# Power.net
KiCad netlist of a schematic drawn in Altium Designer
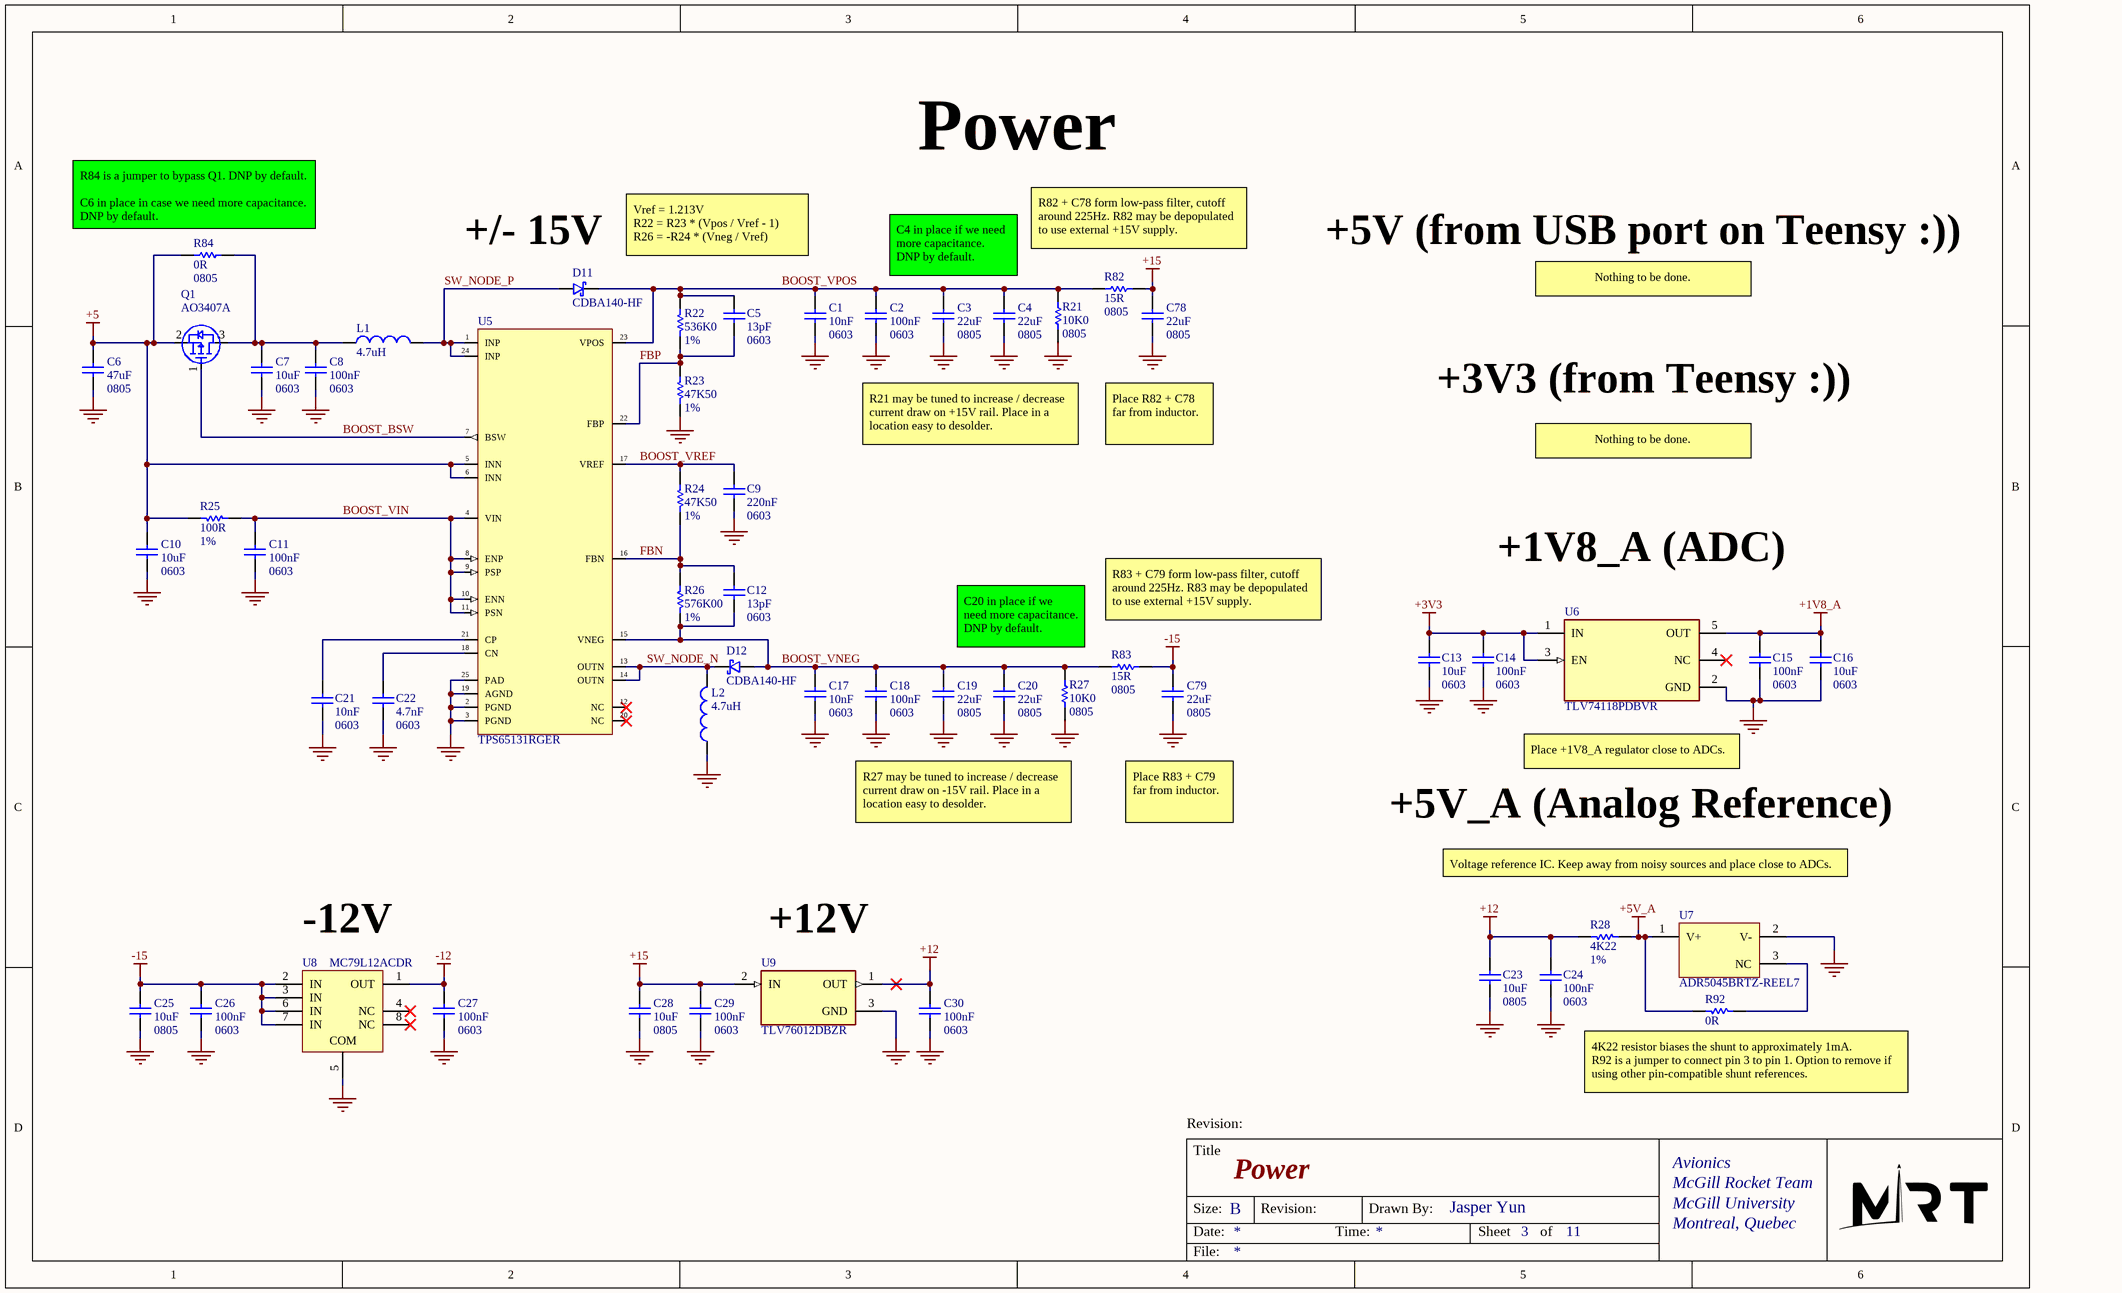
[diagram p0: Power.SchDoc]

(export (version "E")
  (design (tool "Eeschema 10.0.6"))
  (components
    (comp (ref "C1")
      (value "10nF")
      (footprint "0603 CAP SAMSUNG CL10C")
      (description "Capacitor")
      (fields (field (name "ALTIUM_VALUE") "0603") (field (name "PUBLISHER") "Altium Limited"))
      (libsource (lib "Miscellaneous Devices") (part "Cap"))
    )
    (comp (ref "C2")
      (value "100nF")
      (footprint "0603 CAP SAMSUNG CL10C")
      (description "Capacitor")
      (fields (field (name "ALTIUM_VALUE") "0603") (field (name "PUBLISHER") "Altium Limited"))
      (libsource (lib "Miscellaneous Devices") (part "Cap"))
    )
    (comp (ref "C3")
      (value "22uF")
      (footprint "0805 CAP")
      (description "Capacitor")
      (fields (field (name "ALTIUM_VALUE") "0805") (field (name "PUBLISHER") "Altium Limited"))
      (libsource (lib "Miscellaneous Devices") (part "Cap"))
    )
    (comp (ref "C4")
      (value "22uF")
      (footprint "0805 CAP")
      (description "Capacitor")
      (fields (field (name "ALTIUM_VALUE") "0805") (field (name "PUBLISHER") "Altium Limited"))
      (libsource (lib "Miscellaneous Devices") (part "Cap"))
    )
    (comp (ref "C5")
      (value "13pF")
      (footprint "0603 CAP SAMSUNG CL10C")
      (description "Capacitor")
      (fields (field (name "ALTIUM_VALUE") "0603") (field (name "PUBLISHER") "Altium Limited"))
      (libsource (lib "Miscellaneous Devices") (part "Cap"))
    )
    (comp (ref "C6")
      (value "47uF")
      (footprint "0805 CAP")
      (description "Capacitor")
      (fields (field (name "ALTIUM_VALUE") "0805") (field (name "PUBLISHER") "Altium Limited"))
      (libsource (lib "Miscellaneous Devices") (part "Cap"))
    )
    (comp (ref "C7")
      (value "10uF")
      (footprint "0603 CAP SAMSUNG CL10C")
      (description "Capacitor")
      (fields (field (name "ALTIUM_VALUE") "0603") (field (name "PUBLISHER") "Altium Limited"))
      (libsource (lib "Miscellaneous Devices") (part "Cap"))
    )
    (comp (ref "C8")
      (value "100nF")
      (footprint "0603 CAP SAMSUNG CL10C")
      (description "Capacitor")
      (fields (field (name "ALTIUM_VALUE") "0603") (field (name "PUBLISHER") "Altium Limited"))
      (libsource (lib "Miscellaneous Devices") (part "Cap"))
    )
    (comp (ref "C9")
      (value "220nF")
      (footprint "0603 CAP SAMSUNG CL10C")
      (description "Capacitor")
      (fields (field (name "ALTIUM_VALUE") "0603") (field (name "PUBLISHER") "Altium Limited"))
      (libsource (lib "Miscellaneous Devices") (part "Cap"))
    )
    (comp (ref "C10")
      (value "10uF")
      (footprint "0603 CAP SAMSUNG CL10C")
      (description "Capacitor")
      (fields (field (name "ALTIUM_VALUE") "0603") (field (name "PUBLISHER") "Altium Limited"))
      (libsource (lib "Miscellaneous Devices") (part "Cap"))
    )
    (comp (ref "C11")
      (value "100nF")
      (footprint "0603 CAP SAMSUNG CL10C")
      (description "Capacitor")
      (fields (field (name "ALTIUM_VALUE") "0603") (field (name "PUBLISHER") "Altium Limited"))
      (libsource (lib "Miscellaneous Devices") (part "Cap"))
    )
    (comp (ref "C12")
      (value "13pF")
      (footprint "0603 CAP SAMSUNG CL10C")
      (description "Capacitor")
      (fields (field (name "ALTIUM_VALUE") "0603") (field (name "PUBLISHER") "Altium Limited"))
      (libsource (lib "Miscellaneous Devices") (part "Cap"))
    )
    (comp (ref "C13")
      (value "10uF")
      (footprint "0603 CAP SAMSUNG CL10C")
      (description "Capacitor")
      (fields (field (name "ALTIUM_VALUE") "0603") (field (name "PUBLISHER") "Altium Limited"))
      (libsource (lib "Miscellaneous Devices") (part "Cap"))
    )
    (comp (ref "C14")
      (value "100nF")
      (footprint "0603 CAP SAMSUNG CL10C")
      (description "Capacitor")
      (fields (field (name "ALTIUM_VALUE") "0603") (field (name "PUBLISHER") "Altium Limited"))
      (libsource (lib "Miscellaneous Devices") (part "Cap"))
    )
    (comp (ref "C15")
      (value "100nF")
      (footprint "0603 CAP SAMSUNG CL10C")
      (description "Capacitor")
      (fields (field (name "ALTIUM_VALUE") "0603") (field (name "PUBLISHER") "Altium Limited"))
      (libsource (lib "Miscellaneous Devices") (part "Cap"))
    )
    (comp (ref "C16")
      (value "10uF")
      (footprint "0603 CAP SAMSUNG CL10C")
      (description "Capacitor")
      (fields (field (name "ALTIUM_VALUE") "0603") (field (name "PUBLISHER") "Altium Limited"))
      (libsource (lib "Miscellaneous Devices") (part "Cap"))
    )
    (comp (ref "C17")
      (value "10nF")
      (footprint "0603 CAP SAMSUNG CL10C")
      (description "Capacitor")
      (fields (field (name "ALTIUM_VALUE") "0603") (field (name "PUBLISHER") "Altium Limited"))
      (libsource (lib "Miscellaneous Devices") (part "Cap"))
    )
    (comp (ref "C18")
      (value "100nF")
      (footprint "0603 CAP SAMSUNG CL10C")
      (description "Capacitor")
      (fields (field (name "ALTIUM_VALUE") "0603") (field (name "PUBLISHER") "Altium Limited"))
      (libsource (lib "Miscellaneous Devices") (part "Cap"))
    )
    (comp (ref "C19")
      (value "22uF")
      (footprint "0805 CAP")
      (description "Capacitor")
      (fields (field (name "ALTIUM_VALUE") "0805") (field (name "PUBLISHER") "Altium Limited"))
      (libsource (lib "Miscellaneous Devices") (part "Cap"))
    )
    (comp (ref "C20")
      (value "22uF")
      (footprint "0805 CAP")
      (description "Capacitor")
      (fields (field (name "ALTIUM_VALUE") "0805") (field (name "PUBLISHER") "Altium Limited"))
      (libsource (lib "Miscellaneous Devices") (part "Cap"))
    )
    (comp (ref "C21")
      (value "10nF")
      (footprint "0603 CAP SAMSUNG CL10C")
      (description "Capacitor")
      (fields (field (name "ALTIUM_VALUE") "0603") (field (name "PUBLISHER") "Altium Limited"))
      (libsource (lib "Miscellaneous Devices") (part "Cap"))
    )
    (comp (ref "C22")
      (value "4.7nF")
      (footprint "0603 CAP SAMSUNG CL10C")
      (description "Capacitor")
      (fields (field (name "ALTIUM_VALUE") "0603") (field (name "PUBLISHER") "Altium Limited"))
      (libsource (lib "Miscellaneous Devices") (part "Cap"))
    )
    (comp (ref "C23")
      (value "10uF")
      (footprint "0805 CAP")
      (description "Capacitor")
      (fields (field (name "ALTIUM_VALUE") "0805") (field (name "PUBLISHER") "Altium Limited"))
      (libsource (lib "Miscellaneous Devices") (part "Cap"))
    )
    (comp (ref "C24")
      (value "100nF")
      (footprint "0603 CAP SAMSUNG CL10C")
      (description "Capacitor")
      (fields (field (name "ALTIUM_VALUE") "0603") (field (name "PUBLISHER") "Altium Limited"))
      (libsource (lib "Miscellaneous Devices") (part "Cap"))
    )
    (comp (ref "C25")
      (value "10uF")
      (footprint "0805 CAP")
      (description "Capacitor")
      (fields (field (name "ALTIUM_VALUE") "0805") (field (name "PUBLISHER") "Altium Limited"))
      (libsource (lib "Miscellaneous Devices") (part "Cap"))
    )
    (comp (ref "C26")
      (value "100nF")
      (footprint "0603 CAP SAMSUNG CL10C")
      (description "Capacitor")
      (fields (field (name "ALTIUM_VALUE") "0603") (field (name "PUBLISHER") "Altium Limited"))
      (libsource (lib "Miscellaneous Devices") (part "Cap"))
    )
    (comp (ref "C27")
      (value "100nF")
      (footprint "0603 CAP SAMSUNG CL10C")
      (description "Capacitor")
      (fields (field (name "ALTIUM_VALUE") "0603") (field (name "PUBLISHER") "Altium Limited"))
      (libsource (lib "Miscellaneous Devices") (part "Cap"))
    )
    (comp (ref "C28")
      (value "10uF")
      (footprint "0805 CAP")
      (description "Capacitor")
      (fields (field (name "ALTIUM_VALUE") "0805") (field (name "PUBLISHER") "Altium Limited"))
      (libsource (lib "Miscellaneous Devices") (part "Cap"))
    )
    (comp (ref "C29")
      (value "100nF")
      (footprint "0603 CAP SAMSUNG CL10C")
      (description "Capacitor")
      (fields (field (name "ALTIUM_VALUE") "0603") (field (name "PUBLISHER") "Altium Limited"))
      (libsource (lib "Miscellaneous Devices") (part "Cap"))
    )
    (comp (ref "C30")
      (value "100nF")
      (footprint "0603 CAP SAMSUNG CL10C")
      (description "Capacitor")
      (fields (field (name "ALTIUM_VALUE") "0603") (field (name "PUBLISHER") "Altium Limited"))
      (libsource (lib "Miscellaneous Devices") (part "Cap"))
    )
    (comp (ref "C78")
      (value "22uF")
      (footprint "0805 CAP")
      (description "Capacitor")
      (fields (field (name "ALTIUM_VALUE") "0805") (field (name "PUBLISHER") "Altium Limited"))
      (libsource (lib "Miscellaneous Devices") (part "Cap"))
    )
    (comp (ref "C79")
      (value "22uF")
      (footprint "0805 CAP")
      (description "Capacitor")
      (fields (field (name "ALTIUM_VALUE") "0805") (field (name "PUBLISHER") "Altium Limited"))
      (libsource (lib "Miscellaneous Devices") (part "Cap"))
    )
    (comp (ref "D11")
      (value "CDBA140-HF")
      (footprint "Diode SMA")
      (description "Generic Schottky Diode")
      (libsource (lib "MRT SCH Library") (part "Schottky Diode"))
    )
    (comp (ref "D12")
      (value "CDBA140-HF")
      (footprint "Diode SMA")
      (description "Generic Schottky Diode")
      (libsource (lib "MRT SCH Library") (part "Schottky Diode"))
    )
    (comp (ref "L1")
      (value "4.7uH")
      (footprint "Inductor BWVS005050403R3M00")
      (description "4.7uH  BWVS005050404R7M00")
      (fields (field (name "PUBLISHER") "Altium Limited"))
      (libsource (lib "Miscellaneous Devices") (part "Inductor"))
    )
    (comp (ref "L2")
      (value "4.7uH")
      (footprint "Inductor BWVS005050403R3M00")
      (description "4.7uH  BWVS005050404R7M00")
      (fields (field (name "PUBLISHER") "Altium Limited"))
      (libsource (lib "Miscellaneous Devices") (part "Inductor"))
    )
    (comp (ref "Q1")
      (value "AO3407A")
      (footprint "SOT23-3")
      (description "AO3407A PMOS")
      (libsource (lib "MRT SCH Library") (part "PMOS"))
    )
    (comp (ref "R21")
      (value "10K0")
      (footprint "0805 RES")
      (description "Resistor")
      (fields (field (name "ALTIUM_VALUE") "0805") (field (name "PUBLISHER") "Altium Limited"))
      (libsource (lib "Miscellaneous Devices") (part "Res1"))
    )
    (comp (ref "R22")
      (value "536K0")
      (footprint "0603 RES")
      (description "Resistor")
      (fields (field (name "ALTIUM_VALUE") "1%") (field (name "PUBLISHER") "Altium Limited"))
      (libsource (lib "Miscellaneous Devices") (part "Res1"))
    )
    (comp (ref "R23")
      (value "47K50")
      (footprint "0603 RES")
      (description "Resistor")
      (fields (field (name "ALTIUM_VALUE") "1%") (field (name "PUBLISHER") "Altium Limited"))
      (libsource (lib "Miscellaneous Devices") (part "Res1"))
    )
    (comp (ref "R24")
      (value "47K50")
      (footprint "0603 RES")
      (description "Resistor")
      (fields (field (name "ALTIUM_VALUE") "1%") (field (name "PUBLISHER") "Altium Limited"))
      (libsource (lib "Miscellaneous Devices") (part "Res1"))
    )
    (comp (ref "R25")
      (value "100R")
      (footprint "0603 RES")
      (description "Resistor")
      (fields (field (name "ALTIUM_VALUE") "1%") (field (name "PUBLISHER") "Altium Limited"))
      (libsource (lib "Miscellaneous Devices") (part "Res1"))
    )
    (comp (ref "R26")
      (value "576K00")
      (footprint "0603 RES")
      (description "Resistor")
      (fields (field (name "ALTIUM_VALUE") "1%") (field (name "PUBLISHER") "Altium Limited"))
      (libsource (lib "Miscellaneous Devices") (part "Res1"))
    )
    (comp (ref "R27")
      (value "10K0")
      (footprint "0805 RES")
      (description "Resistor")
      (fields (field (name "ALTIUM_VALUE") "0805") (field (name "PUBLISHER") "Altium Limited"))
      (libsource (lib "Miscellaneous Devices") (part "Res1"))
    )
    (comp (ref "R28")
      (value "4K22")
      (footprint "0603 RES")
      (description "Resistor")
      (fields (field (name "ALTIUM_VALUE") "1%") (field (name "PUBLISHER") "Altium Limited"))
      (libsource (lib "Miscellaneous Devices") (part "Res1"))
    )
    (comp (ref "R82")
      (value "15R")
      (footprint "0805 RES")
      (description "Resistor")
      (fields (field (name "ALTIUM_VALUE") "0805") (field (name "PUBLISHER") "Altium Limited"))
      (libsource (lib "Miscellaneous Devices") (part "Res1"))
    )
    (comp (ref "R83")
      (value "15R")
      (footprint "0805 RES")
      (description "Resistor")
      (fields (field (name "ALTIUM_VALUE") "0805") (field (name "PUBLISHER") "Altium Limited"))
      (libsource (lib "Miscellaneous Devices") (part "Res1"))
    )
    (comp (ref "R84")
      (value "0R")
      (footprint "0805 RES")
      (description "Resistor")
      (fields (field (name "ALTIUM_VALUE") "0805") (field (name "PUBLISHER") "Altium Limited"))
      (libsource (lib "Miscellaneous Devices") (part "Res1"))
    )
    (comp (ref "R92")
      (value "0R")
      (footprint "0603 RES")
      (description "Resistor")
      (fields (field (name "PUBLISHER") "Altium Limited"))
      (libsource (lib "Miscellaneous Devices") (part "Res1"))
    )
    (comp (ref "U5")
      (value "TPS65131RGER")
      (footprint "VQFN-24")
      (description "IC REG BUCK BST INV ADJ DL 24QFN")
      (fields (field (name "MANUFACTURER") "Texas Instruments"))
      (libsource (lib "MRT SCH Library") (part "Dual Boost TPS65131RGER"))
    )
    (comp (ref "U6")
      (value "TLV74118PDBVR")
      (footprint "FP-DBV0005A-IPC_A")
      (description "None")
      (libsource (lib "Altium Content Vault") (part "843f007849b3ee74adb27ff62509038"))
    )
    (comp (ref "U7")
      (value "ADR5045BRTZ-REEL7")
      (footprint "ADI-RT-3_M")
      (fields (field (name "MANUFACTURER") "Analog Devices"))
      (libsource (lib "Altium Content Vault") (part "ADI-ADR158x_504x-RT_KS-3"))
    )
    (comp (ref "U8")
      (value "MC79L12ACDR")
      (footprint "D0008A_M")
      (fields (field (name "MANUFACTURER") "Texas Instruments"))
      (libsource (lib "Altium Content Vault") (part "TI-MC79L12AD8"))
    )
    (comp (ref "U9")
      (value "TLV76012DBZR")
      (footprint "FP-DBZ0003A-IPC_A")
      (description "IC REG LINEAR 12V 100MA SOT23-3")
      (libsource (lib "Altium Content Vault") (part "194d833bae470731f3ec9529f7c1b5f"))
    )
  )
  (nets
    (net (code "1") (name "+1V8_A") (class "Default")
      (node (ref "C15") (pin "2") (pinfunction "2_2") (pintype "passive"))
      (node (ref "C16") (pin "2") (pinfunction "2_2") (pintype "passive"))
      (node (ref "U6") (pin "5") (pinfunction "OUT_5") (pintype "power_in"))
    )
    (net (code "2") (name "+3V3") (class "Default")
      (node (ref "C13") (pin "2") (pinfunction "2_2") (pintype "passive"))
      (node (ref "C14") (pin "2") (pinfunction "2_2") (pintype "passive"))
      (node (ref "U6") (pin "1") (pinfunction "IN_1") (pintype "power_in"))
      (node (ref "U6") (pin "3") (pinfunction "EN_3") (pintype "input"))
    )
    (net (code "3") (name "+5") (class "Default")
      (node (ref "C10") (pin "2") (pinfunction "2_2") (pintype "passive"))
      (node (ref "C6") (pin "2") (pinfunction "2_2") (pintype "passive"))
      (node (ref "Q1") (pin "2") (pinfunction "Source_2") (pintype "passive"))
      (node (ref "R25") (pin "1") (pinfunction "1_1") (pintype "passive"))
      (node (ref "R84") (pin "2") (pinfunction "2_2") (pintype "passive"))
      (node (ref "U5") (pin "5") (pinfunction "INN_5") (pintype "passive"))
      (node (ref "U5") (pin "6") (pinfunction "INN_6") (pintype "passive"))
    )
    (net (code "4") (name "+5V_A") (class "Default")
      (node (ref "R28") (pin "2") (pinfunction "2_2") (pintype "passive"))
      (node (ref "R92") (pin "1") (pinfunction "1_1") (pintype "passive"))
      (node (ref "U7") (pin "1") (pinfunction "V+_1") (pintype "power_in"))
    )
    (net (code "5") (name "+12") (class "Default")
      (node (ref "C23") (pin "2") (pinfunction "2_2") (pintype "passive"))
      (node (ref "C24") (pin "2") (pinfunction "2_2") (pintype "passive"))
      (node (ref "C30") (pin "2") (pinfunction "2_2") (pintype "passive"))
      (node (ref "R28") (pin "1") (pinfunction "1_1") (pintype "passive"))
      (node (ref "U9") (pin "1") (pinfunction "OUT_1") (pintype "output"))
    )
    (net (code "6") (name "+15") (class "Default")
      (node (ref "C28") (pin "2") (pinfunction "2_2") (pintype "passive"))
      (node (ref "C29") (pin "2") (pinfunction "2_2") (pintype "passive"))
      (node (ref "C78") (pin "2") (pinfunction "2_2") (pintype "passive"))
      (node (ref "R82") (pin "1") (pinfunction "1_1") (pintype "passive"))
      (node (ref "U9") (pin "2") (pinfunction "IN_2") (pintype "input"))
    )
    (net (code "7") (name "-12") (class "Default")
      (node (ref "C27") (pin "2") (pinfunction "2_2") (pintype "passive"))
      (node (ref "U8") (pin "1") (pinfunction "OUT_1") (pintype "power_in"))
    )
    (net (code "8") (name "-15") (class "Default")
      (node (ref "C25") (pin "2") (pinfunction "2_2") (pintype "passive"))
      (node (ref "C26") (pin "2") (pinfunction "2_2") (pintype "passive"))
      (node (ref "C79") (pin "2") (pinfunction "2_2") (pintype "passive"))
      (node (ref "R83") (pin "1") (pinfunction "1_1") (pintype "passive"))
      (node (ref "U8") (pin "2") (pinfunction "IN_2") (pintype "power_in"))
      (node (ref "U8") (pin "3") (pinfunction "IN_3") (pintype "power_in"))
      (node (ref "U8") (pin "6") (pinfunction "IN_6") (pintype "power_in"))
      (node (ref "U8") (pin "7") (pinfunction "IN_7") (pintype "power_in"))
    )
    (net (code "9") (name "/BOOST_BSW") (class "Default")
      (node (ref "Q1") (pin "1") (pinfunction "Gate_1") (pintype "passive"))
      (node (ref "U5") (pin "7") (pinfunction "BSW_7") (pintype "output"))
    )
    (net (code "10") (name "/BOOST_VIN") (class "Default")
      (node (ref "C11") (pin "2") (pinfunction "2_2") (pintype "passive"))
      (node (ref "R25") (pin "2") (pinfunction "2_2") (pintype "passive"))
      (node (ref "U5") (pin "10") (pinfunction "ENN_10") (pintype "input"))
      (node (ref "U5") (pin "11") (pinfunction "PSN_11") (pintype "input"))
      (node (ref "U5") (pin "4") (pinfunction "VIN_4") (pintype "passive"))
      (node (ref "U5") (pin "8") (pinfunction "ENP_8") (pintype "input"))
      (node (ref "U5") (pin "9") (pinfunction "PSP_9") (pintype "input"))
    )
    (net (code "11") (name "/BOOST_VNEG") (class "Default")
      (node (ref "C12") (pin "1") (pinfunction "1_1") (pintype "passive"))
      (node (ref "C17") (pin "2") (pinfunction "2_2") (pintype "passive"))
      (node (ref "C18") (pin "2") (pinfunction "2_2") (pintype "passive"))
      (node (ref "C19") (pin "2") (pinfunction "2_2") (pintype "passive"))
      (node (ref "C20") (pin "2") (pinfunction "2_2") (pintype "passive"))
      (node (ref "D12") (pin "2") (pinfunction "Anode_2") (pintype "passive"))
      (node (ref "R26") (pin "1") (pinfunction "1_1") (pintype "passive"))
      (node (ref "R27") (pin "2") (pinfunction "2_2") (pintype "passive"))
      (node (ref "R83") (pin "2") (pinfunction "2_2") (pintype "passive"))
      (node (ref "U5") (pin "15") (pinfunction "VNEG_15") (pintype "passive"))
    )
    (net (code "12") (name "/BOOST_VPOS") (class "Default")
      (node (ref "C1") (pin "2") (pinfunction "2_2") (pintype "passive"))
      (node (ref "C2") (pin "2") (pinfunction "2_2") (pintype "passive"))
      (node (ref "C3") (pin "2") (pinfunction "2_2") (pintype "passive"))
      (node (ref "C4") (pin "2") (pinfunction "2_2") (pintype "passive"))
      (node (ref "C5") (pin "1") (pinfunction "1_1") (pintype "passive"))
      (node (ref "D11") (pin "1") (pinfunction "Cathode_1") (pintype "passive"))
      (node (ref "R21") (pin "2") (pinfunction "2_2") (pintype "passive"))
      (node (ref "R22") (pin "1") (pinfunction "1_1") (pintype "passive"))
      (node (ref "R82") (pin "2") (pinfunction "2_2") (pintype "passive"))
      (node (ref "U5") (pin "23") (pinfunction "VPOS_23") (pintype "passive"))
    )
    (net (code "13") (name "/BOOST_VREF") (class "Default")
      (node (ref "C9") (pin "1") (pinfunction "1_1") (pintype "passive"))
      (node (ref "R24") (pin "1") (pinfunction "1_1") (pintype "passive"))
      (node (ref "U5") (pin "17") (pinfunction "VREF_17") (pintype "passive"))
    )
    (net (code "14") (name "/FBN") (class "Default")
      (node (ref "C12") (pin "2") (pinfunction "2_2") (pintype "passive"))
      (node (ref "R24") (pin "2") (pinfunction "2_2") (pintype "passive"))
      (node (ref "R26") (pin "2") (pinfunction "2_2") (pintype "passive"))
      (node (ref "U5") (pin "16") (pinfunction "FBN_16") (pintype "passive"))
    )
    (net (code "15") (name "/FBP") (class "Default")
      (node (ref "C5") (pin "2") (pinfunction "2_2") (pintype "passive"))
      (node (ref "R22") (pin "2") (pinfunction "2_2") (pintype "passive"))
      (node (ref "R23") (pin "1") (pinfunction "1_1") (pintype "passive"))
      (node (ref "U5") (pin "22") (pinfunction "FBP_22") (pintype "passive"))
    )
    (net (code "16") (name "/SW_NODE_N") (class "Default")
      (node (ref "D12") (pin "1") (pinfunction "Cathode_1") (pintype "passive"))
      (node (ref "L2") (pin "2") (pinfunction "2_2") (pintype "passive"))
      (node (ref "U5") (pin "13") (pinfunction "OUTN_13") (pintype "passive"))
      (node (ref "U5") (pin "14") (pinfunction "OUTN_14") (pintype "passive"))
    )
    (net (code "17") (name "/SW_NODE_P") (class "Default")
      (node (ref "D11") (pin "2") (pinfunction "Anode_2") (pintype "passive"))
      (node (ref "L1") (pin "2") (pinfunction "2_2") (pintype "passive"))
      (node (ref "U5") (pin "1") (pinfunction "INP_1") (pintype "passive"))
      (node (ref "U5") (pin "24") (pinfunction "INP_24") (pintype "passive"))
    )
    (net (code "18") (name "GND") (class "Default")
      (node (ref "C1") (pin "1") (pinfunction "1_1") (pintype "passive"))
      (node (ref "C10") (pin "1") (pinfunction "1_1") (pintype "passive"))
      (node (ref "C11") (pin "1") (pinfunction "1_1") (pintype "passive"))
      (node (ref "C13") (pin "1") (pinfunction "1_1") (pintype "passive"))
      (node (ref "C14") (pin "1") (pinfunction "1_1") (pintype "passive"))
      (node (ref "C15") (pin "1") (pinfunction "1_1") (pintype "passive"))
      (node (ref "C16") (pin "1") (pinfunction "1_1") (pintype "passive"))
      (node (ref "C17") (pin "1") (pinfunction "1_1") (pintype "passive"))
      (node (ref "C18") (pin "1") (pinfunction "1_1") (pintype "passive"))
      (node (ref "C19") (pin "1") (pinfunction "1_1") (pintype "passive"))
      (node (ref "C2") (pin "1") (pinfunction "1_1") (pintype "passive"))
      (node (ref "C20") (pin "1") (pinfunction "1_1") (pintype "passive"))
      (node (ref "C21") (pin "1") (pinfunction "1_1") (pintype "passive"))
      (node (ref "C22") (pin "1") (pinfunction "1_1") (pintype "passive"))
      (node (ref "C23") (pin "1") (pinfunction "1_1") (pintype "passive"))
      (node (ref "C24") (pin "1") (pinfunction "1_1") (pintype "passive"))
      (node (ref "C25") (pin "1") (pinfunction "1_1") (pintype "passive"))
      (node (ref "C26") (pin "1") (pinfunction "1_1") (pintype "passive"))
      (node (ref "C27") (pin "1") (pinfunction "1_1") (pintype "passive"))
      (node (ref "C28") (pin "1") (pinfunction "1_1") (pintype "passive"))
      (node (ref "C29") (pin "1") (pinfunction "1_1") (pintype "passive"))
      (node (ref "C3") (pin "1") (pinfunction "1_1") (pintype "passive"))
      (node (ref "C30") (pin "1") (pinfunction "1_1") (pintype "passive"))
      (node (ref "C4") (pin "1") (pinfunction "1_1") (pintype "passive"))
      (node (ref "C6") (pin "1") (pinfunction "1_1") (pintype "passive"))
      (node (ref "C7") (pin "1") (pinfunction "1_1") (pintype "passive"))
      (node (ref "C78") (pin "1") (pinfunction "1_1") (pintype "passive"))
      (node (ref "C79") (pin "1") (pinfunction "1_1") (pintype "passive"))
      (node (ref "C8") (pin "1") (pinfunction "1_1") (pintype "passive"))
      (node (ref "C9") (pin "2") (pinfunction "2_2") (pintype "passive"))
      (node (ref "L2") (pin "1") (pinfunction "1_1") (pintype "passive"))
      (node (ref "R21") (pin "1") (pinfunction "1_1") (pintype "passive"))
      (node (ref "R23") (pin "2") (pinfunction "2_2") (pintype "passive"))
      (node (ref "R27") (pin "1") (pinfunction "1_1") (pintype "passive"))
      (node (ref "U5") (pin "19") (pinfunction "AGND_19") (pintype "passive"))
      (node (ref "U5") (pin "2") (pinfunction "PGND_2") (pintype "passive"))
      (node (ref "U5") (pin "25") (pinfunction "PAD_25") (pintype "passive"))
      (node (ref "U5") (pin "3") (pinfunction "PGND_3") (pintype "passive"))
      (node (ref "U6") (pin "2") (pinfunction "GND_2") (pintype "power_in"))
      (node (ref "U7") (pin "2") (pinfunction "V-_2") (pintype "power_in"))
      (node (ref "U8") (pin "5") (pinfunction "COM_5") (pintype "power_in"))
      (node (ref "U9") (pin "3") (pinfunction "GND_3") (pintype "power_in"))
    )
    (net (code "19") (name "Net-(Q1-Drain)") (class "Default")
      (node (ref "C7") (pin "2") (pinfunction "2_2") (pintype "passive"))
      (node (ref "C8") (pin "2") (pinfunction "2_2") (pintype "passive"))
      (node (ref "L1") (pin "1") (pinfunction "1_1") (pintype "passive"))
      (node (ref "Q1") (pin "3") (pinfunction "Drain_3") (pintype "passive"))
      (node (ref "R84") (pin "1") (pinfunction "1_1") (pintype "passive"))
    )
    (net (code "20") (name "Net-(U5-CN)") (class "Default")
      (node (ref "C22") (pin "2") (pinfunction "2_2") (pintype "passive"))
      (node (ref "U5") (pin "18") (pinfunction "CN_18") (pintype "passive"))
    )
    (net (code "21") (name "Net-(U5-CP)") (class "Default")
      (node (ref "C21") (pin "2") (pinfunction "2_2") (pintype "passive"))
      (node (ref "U5") (pin "21") (pinfunction "CP_21") (pintype "passive"))
    )
    (net (code "22") (name "Net-(U7-NC)") (class "Default")
      (node (ref "R92") (pin "2") (pinfunction "2_2") (pintype "passive"))
      (node (ref "U7") (pin "3") (pinfunction "NC_3") (pintype "passive"))
    )
    (net (code "23") (name "unconnected-(U5-NC-Pad12)") (class "Default")
      (node (ref "U5") (pin "12") (pinfunction "NC_12") (pintype "passive+no_connect"))
    )
    (net (code "24") (name "unconnected-(U5-NC-Pad20)") (class "Default")
      (node (ref "U5") (pin "20") (pinfunction "NC_20") (pintype "passive+no_connect"))
    )
    (net (code "25") (name "unconnected-(U6-NC-Pad4)") (class "Default")
      (node (ref "U6") (pin "4") (pinfunction "NC_4") (pintype "passive+no_connect"))
    )
    (net (code "26") (name "unconnected-(U8-NC-Pad4)") (class "Default")
      (node (ref "U8") (pin "4") (pinfunction "NC_4") (pintype "passive+no_connect"))
    )
    (net (code "27") (name "unconnected-(U8-NC-Pad8)") (class "Default")
      (node (ref "U8") (pin "8") (pinfunction "NC_8") (pintype "passive+no_connect"))
    )
  )
)
